# CHARGE_MONITORING_CIRCUIT.net
KiCad netlist of a schematic drawn in EasyEDA
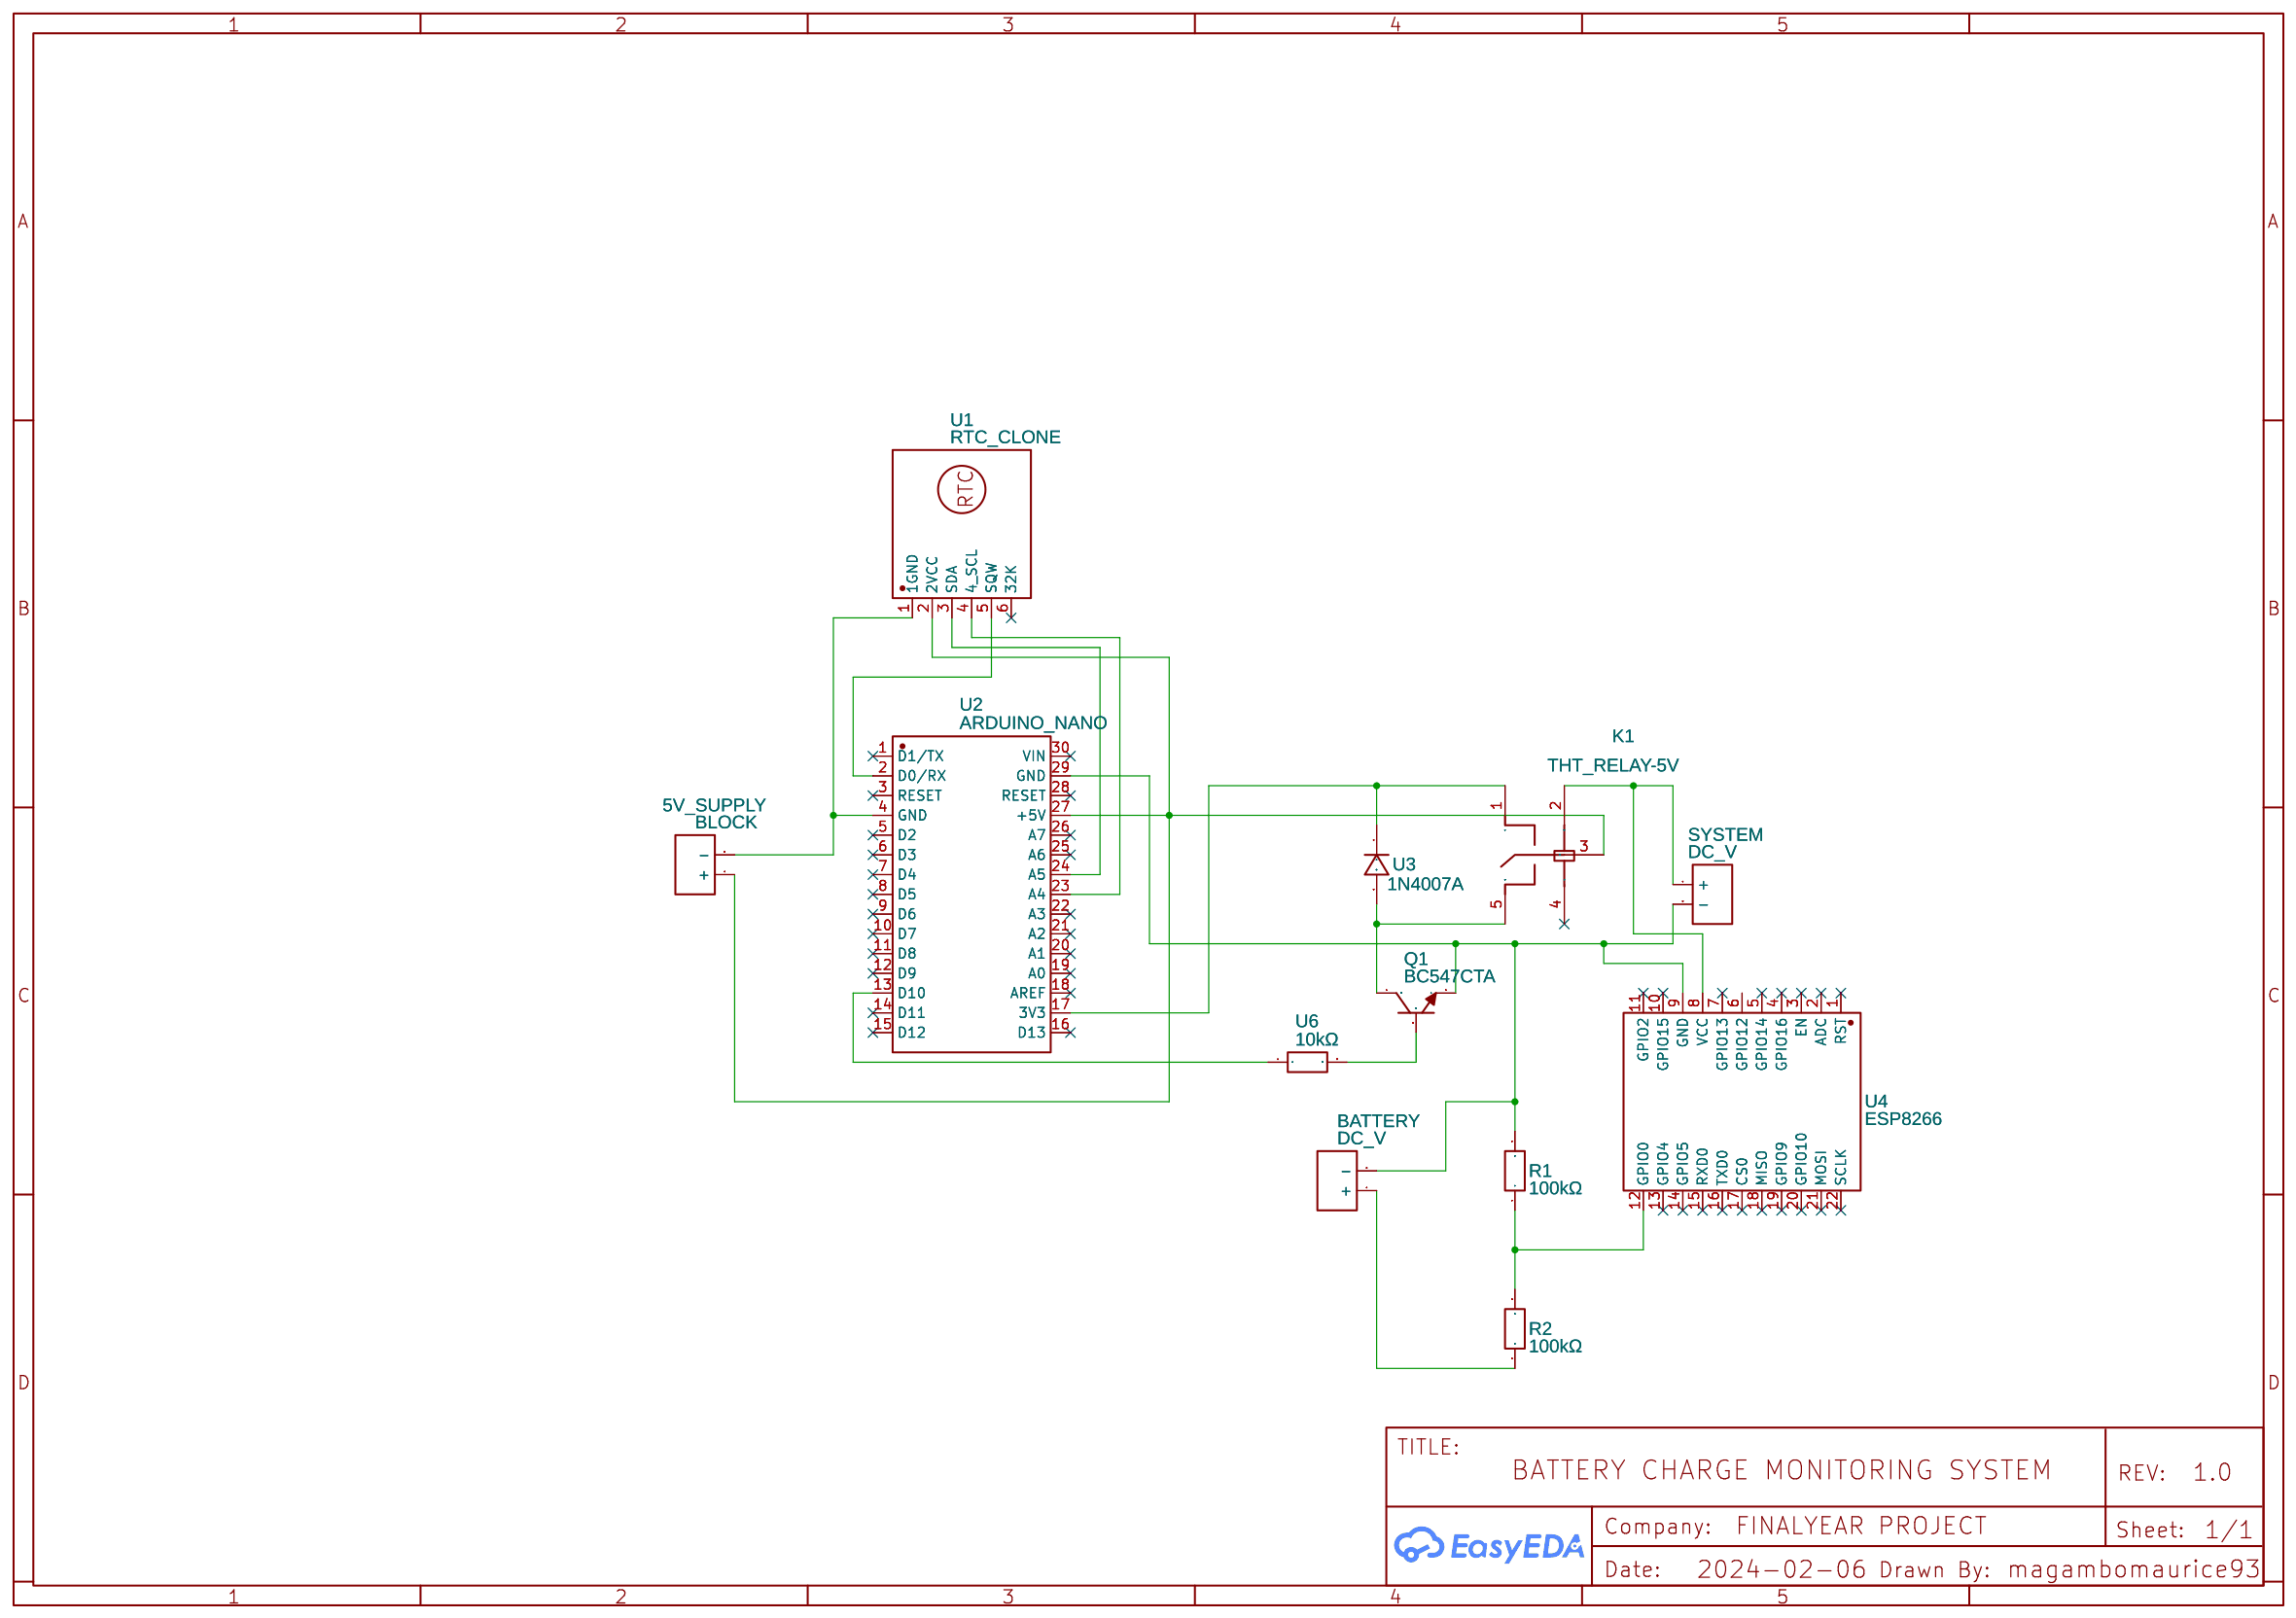
[diagram p0: schematic sheet]

(export (version "E")
  (design (tool "Eeschema 10.0.6"))
  (components
    (comp (ref "5V_SUPPLY") (value "BLOCK") (libsource (lib "") (part "DC_V")))
    (comp (ref "BATTERY") (value "DC_V") (libsource (lib "") (part "DC_V_2")))
    (comp (ref "K1")
      (value "THT_RELAY-5V")
      (fields (field (name "Manufacturer Part") "Relay-SPST"))
      (libsource (lib "") (part "THT_RELAY-SPST_5V"))
    )
    (comp (ref "Q1")
      (value "BC547CTA")
      (fields (field (name "Manufacturer") "onsemi(安森美)"))
      (libsource (lib "") (part "BC547CTA"))
    )
    (comp (ref "R1")
      (value "100kΩ")
      (fields
        (field (name "Manufacturer Part") "RNF14FAE100K")
        (field (name "Manufacturer") "SEI(Stackpole Electronics Inc.)")
      )
      (libsource (lib "") (part "RNF14FAE100K"))
    )
    (comp (ref "R2")
      (value "100kΩ")
      (fields
        (field (name "Manufacturer Part") "RNF14FAE100K")
        (field (name "Manufacturer") "SEI(Stackpole Electronics Inc.)")
      )
      (libsource (lib "") (part "RNF14FAE100K"))
    )
    (comp (ref "SYSTEM") (value "DC_V") (libsource (lib "") (part "DC_V_1")))
    (comp (ref "U1") (value "RTC_CLONE") (libsource (lib "") (part "RTC_CLONE")))
    (comp (ref "U2") (value "ARDUINO_NANO") (libsource (lib "") (part "ARDUINO_NANO")))
    (comp (ref "U3")
      (value "1N4007A")
      (fields (field (name "Manufacturer") "LRC(乐山无线电)"))
      (libsource (lib "") (part "1N4007A"))
    )
    (comp (ref "U4") (value "ESP8266") (libsource (lib "") (part "ESP8266")))
    (comp (ref "U6")
      (value "10kΩ")
      (fields (field (name "Manufacturer Part") "FM0207FTE52-10K") (field (name "Manufacturer") "YAGEO(国巨)"))
      (libsource (lib "") (part "FM0207FTE52-10K"))
    )
  )
  (nets
    (net (code "1") (name "Net-(5V_SUPPLY-+)") (class "Default")
      (node (ref "5V_SUPPLY") (pin "1") (pinfunction "+_1") (pintype "unspecified"))
      (node (ref "K1") (pin "3") (pinfunction "3_3") (pintype "unspecified"))
      (node (ref "U1") (pin "2") (pinfunction "2VCC_2") (pintype "unspecified"))
      (node (ref "U2") (pin "27") (pinfunction "+5V_27") (pintype "unspecified"))
    )
    (net (code "2") (name "Net-(5V_SUPPLY--)") (class "Default")
      (node (ref "5V_SUPPLY") (pin "2") (pinfunction "-_2") (pintype "unspecified"))
      (node (ref "U1") (pin "1") (pinfunction "1GND_1") (pintype "unspecified"))
      (node (ref "U2") (pin "4") (pinfunction "GND_4") (pintype "unspecified"))
    )
    (net (code "3") (name "Net-(BATTERY-+)") (class "Default")
      (node (ref "BATTERY") (pin "1") (pinfunction "+_1") (pintype "unspecified"))
      (node (ref "R2") (pin "1") (pinfunction "1_1") (pintype "unspecified"))
    )
    (net (code "4") (name "Net-(BATTERY--)") (class "Default")
      (node (ref "BATTERY") (pin "2") (pinfunction "-_2") (pintype "unspecified"))
      (node (ref "Q1") (pin "3") (pinfunction "E_3") (pintype "input"))
      (node (ref "R1") (pin "2") (pinfunction "2_2") (pintype "unspecified"))
      (node (ref "SYSTEM") (pin "2") (pinfunction "-_2") (pintype "unspecified"))
      (node (ref "U2") (pin "29") (pinfunction "GND_29") (pintype "unspecified"))
      (node (ref "U4") (pin "9") (pinfunction "GND_9") (pintype "unspecified"))
    )
    (net (code "5") (name "Net-(Q1-B)") (class "Default")
      (node (ref "Q1") (pin "2") (pinfunction "B_2") (pintype "input"))
      (node (ref "U6") (pin "2") (pinfunction "2_2") (pintype "unspecified"))
    )
    (net (code "6") (name "Net-(Q1-C)") (class "Default")
      (node (ref "K1") (pin "5") (pinfunction "5_5") (pintype "unspecified"))
      (node (ref "Q1") (pin "1") (pinfunction "C_1") (pintype "input"))
      (node (ref "U3") (pin "2") (pinfunction "2_2") (pintype "unspecified"))
    )
    (net (code "7") (name "Net-(SYSTEM-+)") (class "Default")
      (node (ref "K1") (pin "2") (pinfunction "2_2") (pintype "unspecified"))
      (node (ref "SYSTEM") (pin "1") (pinfunction "+_1") (pintype "unspecified"))
      (node (ref "U4") (pin "8") (pinfunction "VCC_8") (pintype "unspecified"))
    )
    (net (code "8") (name "Net-(U1-4_SCL)") (class "Default")
      (node (ref "U1") (pin "4") (pinfunction "4_SCL_4") (pintype "unspecified"))
      (node (ref "U2") (pin "23") (pinfunction "A4_23") (pintype "unspecified"))
    )
    (net (code "9") (name "Net-(U1-SDA)") (class "Default")
      (node (ref "U1") (pin "3") (pinfunction "SDA_3") (pintype "unspecified"))
      (node (ref "U2") (pin "24") (pinfunction "A5_24") (pintype "unspecified"))
    )
    (net (code "10") (name "Net-(U1-SQW)") (class "Default")
      (node (ref "U1") (pin "5") (pinfunction "SQW_5") (pintype "unspecified"))
      (node (ref "U2") (pin "2") (pinfunction "D0/RX_2") (pintype "unspecified"))
    )
    (net (code "11") (name "Net-(U2-3V3)") (class "Default")
      (node (ref "K1") (pin "1") (pinfunction "1_1") (pintype "unspecified"))
      (node (ref "U2") (pin "17") (pinfunction "3V3_17") (pintype "unspecified"))
      (node (ref "U3") (pin "1") (pinfunction "1_1") (pintype "unspecified"))
    )
    (net (code "12") (name "Net-(U2-D10)") (class "Default")
      (node (ref "U2") (pin "13") (pinfunction "D10_13") (pintype "unspecified"))
      (node (ref "U6") (pin "1") (pinfunction "1_1") (pintype "unspecified"))
    )
    (net (code "13") (name "Net-(U4-GPIO0)") (class "Default")
      (node (ref "R1") (pin "1") (pinfunction "1_1") (pintype "unspecified"))
      (node (ref "R2") (pin "2") (pinfunction "2_2") (pintype "unspecified"))
      (node (ref "U4") (pin "12") (pinfunction "GPIO0_12") (pintype "unspecified"))
    )
    (net (code "14") (name "unconnected-(K1-Pad4)") (class "Default")
      (node (ref "K1") (pin "4") (pinfunction "4_4") (pintype "unspecified+no_connect"))
    )
    (net (code "15") (name "unconnected-(U1-32K-Pad6)") (class "Default")
      (node (ref "U1") (pin "6") (pinfunction "32K_6") (pintype "unspecified+no_connect"))
    )
    (net (code "16") (name "unconnected-(U2-A0-Pad19)") (class "Default")
      (node (ref "U2") (pin "19") (pinfunction "A0_19") (pintype "unspecified+no_connect"))
    )
    (net (code "17") (name "unconnected-(U2-A1-Pad20)") (class "Default")
      (node (ref "U2") (pin "20") (pinfunction "A1_20") (pintype "unspecified+no_connect"))
    )
    (net (code "18") (name "unconnected-(U2-A2-Pad21)") (class "Default")
      (node (ref "U2") (pin "21") (pinfunction "A2_21") (pintype "unspecified+no_connect"))
    )
    (net (code "19") (name "unconnected-(U2-A3-Pad22)") (class "Default")
      (node (ref "U2") (pin "22") (pinfunction "A3_22") (pintype "unspecified+no_connect"))
    )
    (net (code "20") (name "unconnected-(U2-A6-Pad25)") (class "Default")
      (node (ref "U2") (pin "25") (pinfunction "A6_25") (pintype "unspecified+no_connect"))
    )
    (net (code "21") (name "unconnected-(U2-A7-Pad26)") (class "Default")
      (node (ref "U2") (pin "26") (pinfunction "A7_26") (pintype "unspecified+no_connect"))
    )
    (net (code "22") (name "unconnected-(U2-AREF-Pad18)") (class "Default")
      (node (ref "U2") (pin "18") (pinfunction "AREF_18") (pintype "unspecified+no_connect"))
    )
    (net (code "23") (name "unconnected-(U2-D1{slash}TX-Pad1)") (class "Default")
      (node (ref "U2") (pin "1") (pinfunction "D1/TX_1") (pintype "unspecified+no_connect"))
    )
    (net (code "24") (name "unconnected-(U2-D2-Pad5)") (class "Default")
      (node (ref "U2") (pin "5") (pinfunction "D2_5") (pintype "unspecified+no_connect"))
    )
    (net (code "25") (name "unconnected-(U2-D3-Pad6)") (class "Default")
      (node (ref "U2") (pin "6") (pinfunction "D3_6") (pintype "unspecified+no_connect"))
    )
    (net (code "26") (name "unconnected-(U2-D4-Pad7)") (class "Default")
      (node (ref "U2") (pin "7") (pinfunction "D4_7") (pintype "unspecified+no_connect"))
    )
    (net (code "27") (name "unconnected-(U2-D5-Pad8)") (class "Default")
      (node (ref "U2") (pin "8") (pinfunction "D5_8") (pintype "unspecified+no_connect"))
    )
    (net (code "28") (name "unconnected-(U2-D6-Pad9)") (class "Default")
      (node (ref "U2") (pin "9") (pinfunction "D6_9") (pintype "unspecified+no_connect"))
    )
    (net (code "29") (name "unconnected-(U2-D7-Pad10)") (class "Default")
      (node (ref "U2") (pin "10") (pinfunction "D7_10") (pintype "unspecified+no_connect"))
    )
    (net (code "30") (name "unconnected-(U2-D8-Pad11)") (class "Default")
      (node (ref "U2") (pin "11") (pinfunction "D8_11") (pintype "unspecified+no_connect"))
    )
    (net (code "31") (name "unconnected-(U2-D9-Pad12)") (class "Default")
      (node (ref "U2") (pin "12") (pinfunction "D9_12") (pintype "unspecified+no_connect"))
    )
    (net (code "32") (name "unconnected-(U2-D11-Pad14)") (class "Default")
      (node (ref "U2") (pin "14") (pinfunction "D11_14") (pintype "unspecified+no_connect"))
    )
    (net (code "33") (name "unconnected-(U2-D12-Pad15)") (class "Default")
      (node (ref "U2") (pin "15") (pinfunction "D12_15") (pintype "unspecified+no_connect"))
    )
    (net (code "34") (name "unconnected-(U2-D13-Pad16)") (class "Default")
      (node (ref "U2") (pin "16") (pinfunction "D13_16") (pintype "unspecified+no_connect"))
    )
    (net (code "35") (name "unconnected-(U2-RESET-Pad3)") (class "Default")
      (node (ref "U2") (pin "3") (pinfunction "RESET_3") (pintype "unspecified+no_connect"))
    )
    (net (code "36") (name "unconnected-(U2-RESET-Pad28)") (class "Default")
      (node (ref "U2") (pin "28") (pinfunction "RESET_28") (pintype "unspecified+no_connect"))
    )
    (net (code "37") (name "unconnected-(U2-VIN-Pad30)") (class "Default")
      (node (ref "U2") (pin "30") (pinfunction "VIN_30") (pintype "unspecified+no_connect"))
    )
    (net (code "38") (name "unconnected-(U4-ADC-Pad2)") (class "Default")
      (node (ref "U4") (pin "2") (pinfunction "ADC_2") (pintype "unspecified+no_connect"))
    )
    (net (code "39") (name "unconnected-(U4-CS0-Pad17)") (class "Default")
      (node (ref "U4") (pin "17") (pinfunction "CS0_17") (pintype "unspecified+no_connect"))
    )
    (net (code "40") (name "unconnected-(U4-EN-Pad3)") (class "Default")
      (node (ref "U4") (pin "3") (pinfunction "EN_3") (pintype "unspecified+no_connect"))
    )
    (net (code "41") (name "unconnected-(U4-GPIO2-Pad11)") (class "Default")
      (node (ref "U4") (pin "11") (pinfunction "GPIO2_11") (pintype "unspecified+no_connect"))
    )
    (net (code "42") (name "unconnected-(U4-GPIO4-Pad13)") (class "Default")
      (node (ref "U4") (pin "13") (pinfunction "GPIO4_13") (pintype "unspecified+no_connect"))
    )
    (net (code "43") (name "unconnected-(U4-GPIO5-Pad14)") (class "Default")
      (node (ref "U4") (pin "14") (pinfunction "GPIO5_14") (pintype "unspecified+no_connect"))
    )
    (net (code "44") (name "unconnected-(U4-GPIO9-Pad19)") (class "Default")
      (node (ref "U4") (pin "19") (pinfunction "GPIO9_19") (pintype "unspecified+no_connect"))
    )
    (net (code "45") (name "unconnected-(U4-GPIO10-Pad20)") (class "Default")
      (node (ref "U4") (pin "20") (pinfunction "GPIO10_20") (pintype "unspecified+no_connect"))
    )
    (net (code "46") (name "unconnected-(U4-GPIO12-Pad6)") (class "Default")
      (node (ref "U4") (pin "6") (pinfunction "GPIO12_6") (pintype "unspecified"))
    )
    (net (code "47") (name "unconnected-(U4-GPIO13-Pad7)") (class "Default")
      (node (ref "U4") (pin "7") (pinfunction "GPIO13_7") (pintype "unspecified+no_connect"))
    )
    (net (code "48") (name "unconnected-(U4-GPIO14-Pad5)") (class "Default")
      (node (ref "U4") (pin "5") (pinfunction "GPIO14_5") (pintype "unspecified+no_connect"))
    )
    (net (code "49") (name "unconnected-(U4-GPIO15-Pad10)") (class "Default")
      (node (ref "U4") (pin "10") (pinfunction "GPIO15_10") (pintype "unspecified+no_connect"))
    )
    (net (code "50") (name "unconnected-(U4-GPIO16-Pad4)") (class "Default")
      (node (ref "U4") (pin "4") (pinfunction "GPIO16_4") (pintype "unspecified+no_connect"))
    )
    (net (code "51") (name "unconnected-(U4-MISO-Pad18)") (class "Default")
      (node (ref "U4") (pin "18") (pinfunction "MISO_18") (pintype "unspecified+no_connect"))
    )
    (net (code "52") (name "unconnected-(U4-MOSI-Pad21)") (class "Default")
      (node (ref "U4") (pin "21") (pinfunction "MOSI_21") (pintype "unspecified+no_connect"))
    )
    (net (code "53") (name "unconnected-(U4-RST-Pad1)") (class "Default")
      (node (ref "U4") (pin "1") (pinfunction "RST_1") (pintype "unspecified+no_connect"))
    )
    (net (code "54") (name "unconnected-(U4-RXD0-Pad15)") (class "Default")
      (node (ref "U4") (pin "15") (pinfunction "RXD0_15") (pintype "unspecified+no_connect"))
    )
    (net (code "55") (name "unconnected-(U4-SCLK-Pad22)") (class "Default")
      (node (ref "U4") (pin "22") (pinfunction "SCLK_22") (pintype "unspecified+no_connect"))
    )
    (net (code "56") (name "unconnected-(U4-TXD0-Pad16)") (class "Default")
      (node (ref "U4") (pin "16") (pinfunction "TXD0_16") (pintype "unspecified+no_connect"))
    )
  )
)
